# Panel.net
KiCad netlist of a schematic drawn in EAGLE
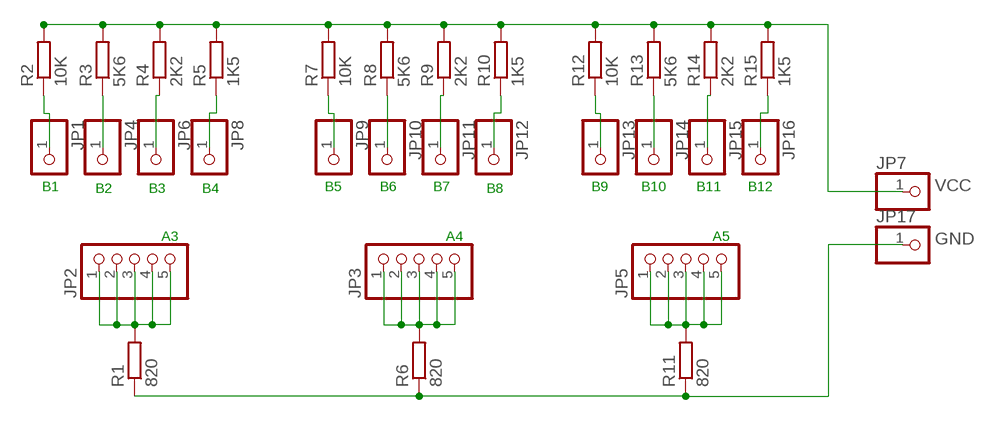
[diagram p0: schematic, sheet 1]

(export (version "E")
  (design (tool "Eeschema 10.0.6"))
  (components
    (comp (ref "JP1")
      (value "PINHD-1X1")
      (footprint "eagle-import:1X01")
      (libsource (lib "eagle-import") (part "PINHD-1X1"))
    )
    (comp (ref "JP2")
      (value "PINHD-1X5")
      (footprint "eagle-import:1X05")
      (libsource (lib "eagle-import") (part "PINHD-1X5"))
    )
    (comp (ref "JP3")
      (value "PINHD-1X5")
      (footprint "eagle-import:1X05")
      (libsource (lib "eagle-import") (part "PINHD-1X5"))
    )
    (comp (ref "JP4")
      (value "PINHD-1X1")
      (footprint "eagle-import:1X01")
      (libsource (lib "eagle-import") (part "PINHD-1X1"))
    )
    (comp (ref "JP5")
      (value "PINHD-1X5")
      (footprint "eagle-import:1X05")
      (libsource (lib "eagle-import") (part "PINHD-1X5"))
    )
    (comp (ref "JP6")
      (value "PINHD-1X1")
      (footprint "eagle-import:1X01")
      (libsource (lib "eagle-import") (part "PINHD-1X1"))
    )
    (comp (ref "JP7")
      (value "PINHD-1X1")
      (footprint "eagle-import:1X01")
      (libsource (lib "eagle-import") (part "PINHD-1X1"))
    )
    (comp (ref "JP8")
      (value "PINHD-1X1")
      (footprint "eagle-import:1X01")
      (libsource (lib "eagle-import") (part "PINHD-1X1"))
    )
    (comp (ref "JP9")
      (value "PINHD-1X1")
      (footprint "eagle-import:1X01")
      (libsource (lib "eagle-import") (part "PINHD-1X1"))
    )
    (comp (ref "JP10")
      (value "PINHD-1X1")
      (footprint "eagle-import:1X01")
      (libsource (lib "eagle-import") (part "PINHD-1X1"))
    )
    (comp (ref "JP11")
      (value "PINHD-1X1")
      (footprint "eagle-import:1X01")
      (libsource (lib "eagle-import") (part "PINHD-1X1"))
    )
    (comp (ref "JP12")
      (value "PINHD-1X1")
      (footprint "eagle-import:1X01")
      (libsource (lib "eagle-import") (part "PINHD-1X1"))
    )
    (comp (ref "JP13")
      (value "PINHD-1X1")
      (footprint "eagle-import:1X01")
      (libsource (lib "eagle-import") (part "PINHD-1X1"))
    )
    (comp (ref "JP14")
      (value "PINHD-1X1")
      (footprint "eagle-import:1X01")
      (libsource (lib "eagle-import") (part "PINHD-1X1"))
    )
    (comp (ref "JP15")
      (value "PINHD-1X1")
      (footprint "eagle-import:1X01")
      (libsource (lib "eagle-import") (part "PINHD-1X1"))
    )
    (comp (ref "JP16")
      (value "PINHD-1X1")
      (footprint "eagle-import:1X01")
      (libsource (lib "eagle-import") (part "PINHD-1X1"))
    )
    (comp (ref "JP17")
      (value "PINHD-1X1")
      (footprint "eagle-import:1X01")
      (libsource (lib "eagle-import") (part "PINHD-1X1"))
    )
    (comp (ref "R1")
      (value "820")
      (footprint "eagle-import:0207_12")
      (libsource (lib "eagle-import") (part "R-EU_0207/12"))
    )
    (comp (ref "R2")
      (value "10K")
      (footprint "eagle-import:0207_12")
      (libsource (lib "eagle-import") (part "R-EU_0207/12"))
    )
    (comp (ref "R3")
      (value "5K6")
      (footprint "eagle-import:0207_12")
      (libsource (lib "eagle-import") (part "R-EU_0207/12"))
    )
    (comp (ref "R4")
      (value "2K2")
      (footprint "eagle-import:0207_12")
      (libsource (lib "eagle-import") (part "R-EU_0207/12"))
    )
    (comp (ref "R5")
      (value "1K5")
      (footprint "eagle-import:0207_12")
      (libsource (lib "eagle-import") (part "R-EU_0207/12"))
    )
    (comp (ref "R6")
      (value "820")
      (footprint "eagle-import:0207_12")
      (libsource (lib "eagle-import") (part "R-EU_0207/12"))
    )
    (comp (ref "R7")
      (value "10K")
      (footprint "eagle-import:0207_12")
      (libsource (lib "eagle-import") (part "R-EU_0207/12"))
    )
    (comp (ref "R8")
      (value "5K6")
      (footprint "eagle-import:0207_12")
      (libsource (lib "eagle-import") (part "R-EU_0207/12"))
    )
    (comp (ref "R9")
      (value "2K2")
      (footprint "eagle-import:0207_12")
      (libsource (lib "eagle-import") (part "R-EU_0207/12"))
    )
    (comp (ref "R10")
      (value "1K5")
      (footprint "eagle-import:0207_12")
      (libsource (lib "eagle-import") (part "R-EU_0207/12"))
    )
    (comp (ref "R11")
      (value "820")
      (footprint "eagle-import:0207_12")
      (libsource (lib "eagle-import") (part "R-EU_0207/12"))
    )
    (comp (ref "R12")
      (value "10K")
      (footprint "eagle-import:0207_12")
      (libsource (lib "eagle-import") (part "R-EU_0207/12"))
    )
    (comp (ref "R13")
      (value "5K6")
      (footprint "eagle-import:0207_12")
      (libsource (lib "eagle-import") (part "R-EU_0207/12"))
    )
    (comp (ref "R14")
      (value "2K2")
      (footprint "eagle-import:0207_12")
      (libsource (lib "eagle-import") (part "R-EU_0207/12"))
    )
    (comp (ref "R15")
      (value "1K5")
      (footprint "eagle-import:0207_12")
      (libsource (lib "eagle-import") (part "R-EU_0207/12"))
    )
  )
  (nets
    (net (code "1") (name "/GND") (class "Default")
      (node (ref "JP17") (pin "1") (pinfunction "1_1") (pintype "passive"))
      (node (ref "R1") (pin "1") (pinfunction "1_1") (pintype "passive"))
      (node (ref "R11") (pin "1") (pinfunction "1_1") (pintype "passive"))
      (node (ref "R6") (pin "1") (pinfunction "1_1") (pintype "passive"))
    )
    (net (code "2") (name "/VCC") (class "Default")
      (node (ref "JP7") (pin "1") (pinfunction "1_1") (pintype "passive"))
      (node (ref "R10") (pin "2") (pinfunction "2_2") (pintype "passive"))
      (node (ref "R12") (pin "2") (pinfunction "2_2") (pintype "passive"))
      (node (ref "R13") (pin "2") (pinfunction "2_2") (pintype "passive"))
      (node (ref "R14") (pin "2") (pinfunction "2_2") (pintype "passive"))
      (node (ref "R15") (pin "2") (pinfunction "2_2") (pintype "passive"))
      (node (ref "R2") (pin "2") (pinfunction "2_2") (pintype "passive"))
      (node (ref "R3") (pin "2") (pinfunction "2_2") (pintype "passive"))
      (node (ref "R4") (pin "2") (pinfunction "2_2") (pintype "passive"))
      (node (ref "R5") (pin "2") (pinfunction "2_2") (pintype "passive"))
      (node (ref "R7") (pin "2") (pinfunction "2_2") (pintype "passive"))
      (node (ref "R8") (pin "2") (pinfunction "2_2") (pintype "passive"))
      (node (ref "R9") (pin "2") (pinfunction "2_2") (pintype "passive"))
    )
    (net (code "3") (name "Net-(JP1-Pad1)") (class "Default")
      (node (ref "JP1") (pin "1") (pinfunction "1_1") (pintype "passive"))
      (node (ref "R2") (pin "1") (pinfunction "1_1") (pintype "passive"))
    )
    (net (code "4") (name "Net-(JP2-Pad1)") (class "Default")
      (node (ref "JP2") (pin "1") (pinfunction "1_1") (pintype "passive"))
      (node (ref "JP2") (pin "2") (pinfunction "2_2") (pintype "passive"))
      (node (ref "JP2") (pin "3") (pinfunction "3_3") (pintype "passive"))
      (node (ref "JP2") (pin "4") (pinfunction "4_4") (pintype "passive"))
      (node (ref "JP2") (pin "5") (pinfunction "5_5") (pintype "passive"))
      (node (ref "R1") (pin "2") (pinfunction "2_2") (pintype "passive"))
    )
    (net (code "5") (name "Net-(JP3-Pad1)") (class "Default")
      (node (ref "JP3") (pin "1") (pinfunction "1_1") (pintype "passive"))
      (node (ref "JP3") (pin "2") (pinfunction "2_2") (pintype "passive"))
      (node (ref "JP3") (pin "3") (pinfunction "3_3") (pintype "passive"))
      (node (ref "JP3") (pin "4") (pinfunction "4_4") (pintype "passive"))
      (node (ref "JP3") (pin "5") (pinfunction "5_5") (pintype "passive"))
      (node (ref "R6") (pin "2") (pinfunction "2_2") (pintype "passive"))
    )
    (net (code "6") (name "Net-(JP4-Pad1)") (class "Default")
      (node (ref "JP4") (pin "1") (pinfunction "1_1") (pintype "passive"))
      (node (ref "R3") (pin "1") (pinfunction "1_1") (pintype "passive"))
    )
    (net (code "7") (name "Net-(JP5-Pad1)") (class "Default")
      (node (ref "JP5") (pin "1") (pinfunction "1_1") (pintype "passive"))
      (node (ref "JP5") (pin "2") (pinfunction "2_2") (pintype "passive"))
      (node (ref "JP5") (pin "3") (pinfunction "3_3") (pintype "passive"))
      (node (ref "JP5") (pin "4") (pinfunction "4_4") (pintype "passive"))
      (node (ref "JP5") (pin "5") (pinfunction "5_5") (pintype "passive"))
      (node (ref "R11") (pin "2") (pinfunction "2_2") (pintype "passive"))
    )
    (net (code "8") (name "Net-(JP6-Pad1)") (class "Default")
      (node (ref "JP6") (pin "1") (pinfunction "1_1") (pintype "passive"))
      (node (ref "R4") (pin "1") (pinfunction "1_1") (pintype "passive"))
    )
    (net (code "9") (name "Net-(JP8-Pad1)") (class "Default")
      (node (ref "JP8") (pin "1") (pinfunction "1_1") (pintype "passive"))
      (node (ref "R5") (pin "1") (pinfunction "1_1") (pintype "passive"))
    )
    (net (code "10") (name "Net-(JP9-Pad1)") (class "Default")
      (node (ref "JP9") (pin "1") (pinfunction "1_1") (pintype "passive"))
      (node (ref "R7") (pin "1") (pinfunction "1_1") (pintype "passive"))
    )
    (net (code "11") (name "Net-(JP10-Pad1)") (class "Default")
      (node (ref "JP10") (pin "1") (pinfunction "1_1") (pintype "passive"))
      (node (ref "R8") (pin "1") (pinfunction "1_1") (pintype "passive"))
    )
    (net (code "12") (name "Net-(JP11-Pad1)") (class "Default")
      (node (ref "JP11") (pin "1") (pinfunction "1_1") (pintype "passive"))
      (node (ref "R9") (pin "1") (pinfunction "1_1") (pintype "passive"))
    )
    (net (code "13") (name "Net-(JP12-Pad1)") (class "Default")
      (node (ref "JP12") (pin "1") (pinfunction "1_1") (pintype "passive"))
      (node (ref "R10") (pin "1") (pinfunction "1_1") (pintype "passive"))
    )
    (net (code "14") (name "Net-(JP13-Pad1)") (class "Default")
      (node (ref "JP13") (pin "1") (pinfunction "1_1") (pintype "passive"))
      (node (ref "R12") (pin "1") (pinfunction "1_1") (pintype "passive"))
    )
    (net (code "15") (name "Net-(JP14-Pad1)") (class "Default")
      (node (ref "JP14") (pin "1") (pinfunction "1_1") (pintype "passive"))
      (node (ref "R13") (pin "1") (pinfunction "1_1") (pintype "passive"))
    )
    (net (code "16") (name "Net-(JP15-Pad1)") (class "Default")
      (node (ref "JP15") (pin "1") (pinfunction "1_1") (pintype "passive"))
      (node (ref "R14") (pin "1") (pinfunction "1_1") (pintype "passive"))
    )
    (net (code "17") (name "Net-(JP16-Pad1)") (class "Default")
      (node (ref "JP16") (pin "1") (pinfunction "1_1") (pintype "passive"))
      (node (ref "R15") (pin "1") (pinfunction "1_1") (pintype "passive"))
    )
  )
)
